# MPU6000.net
KiCad netlist of a schematic drawn in EAGLE
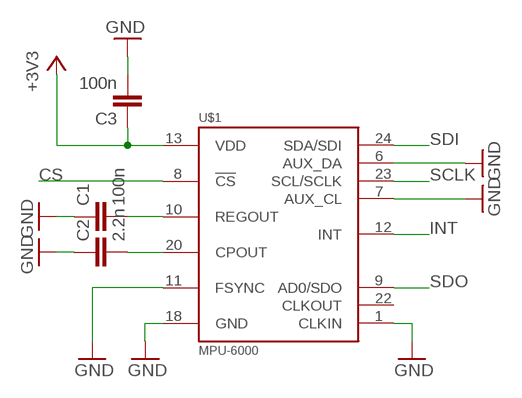
[diagram p0: schematic, sheet 1]

(export (version "E")
  (design (tool "Eeschema 10.0.6"))
  (components
    (comp (ref "C1")
      (value "100n")
      (footprint "eagle-import:C0805")
      (libsource (lib "eagle-import") (part "C-EUC0805"))
    )
    (comp (ref "C2")
      (value "2.2n")
      (footprint "eagle-import:C0805")
      (libsource (lib "eagle-import") (part "C-EUC0805"))
    )
    (comp (ref "C3")
      (value "100n")
      (footprint "eagle-import:C0805")
      (libsource (lib "eagle-import") (part "C-EUC0805"))
    )
    (comp (ref "U$1")
      (value "MPU-6000")
      (footprint "eagle-import:QFN-24")
      (fields (field (name "MF") "InvenSense"))
      (libsource (lib "eagle-import") (part "MPU-6000"))
    )
  )
  (nets
    (net (code "1") (name "+3V3") (class "Default")
      (node (ref "C3") (pin "1") (pinfunction "1_1") (pintype "passive"))
      (node (ref "U$1") (pin "13") (pinfunction "VDD_13") (pintype "bidirectional"))
    )
    (net (code "2") (name "/CS") (class "Default")
      (node (ref "U$1") (pin "8") (pinfunction "~{CS}_8") (pintype "bidirectional"))
    )
    (net (code "3") (name "/INT") (class "Default")
      (node (ref "U$1") (pin "12") (pinfunction "INT_12") (pintype "bidirectional"))
    )
    (net (code "4") (name "/SCLK") (class "Default")
      (node (ref "U$1") (pin "23") (pinfunction "SCL/SCLK_23") (pintype "bidirectional"))
    )
    (net (code "5") (name "/SDI") (class "Default")
      (node (ref "U$1") (pin "24") (pinfunction "SDA/SDI_24") (pintype "bidirectional"))
    )
    (net (code "6") (name "/SDO") (class "Default")
      (node (ref "U$1") (pin "9") (pinfunction "AD0/SDO_9") (pintype "bidirectional"))
    )
    (net (code "7") (name "GND") (class "Default")
      (node (ref "C1") (pin "1") (pinfunction "1_1") (pintype "passive"))
      (node (ref "C2") (pin "1") (pinfunction "1_1") (pintype "passive"))
      (node (ref "C3") (pin "2") (pinfunction "2_2") (pintype "passive"))
      (node (ref "U$1") (pin "1") (pinfunction "CLKIN_1") (pintype "bidirectional"))
      (node (ref "U$1") (pin "11") (pinfunction "FSYNC_11") (pintype "bidirectional"))
      (node (ref "U$1") (pin "18") (pinfunction "GND_18") (pintype "bidirectional"))
      (node (ref "U$1") (pin "6") (pinfunction "AUX_DA_6") (pintype "bidirectional"))
      (node (ref "U$1") (pin "7") (pinfunction "AUX_CL_7") (pintype "bidirectional"))
    )
    (net (code "8") (name "Net-(U$1-CPOUT)") (class "Default")
      (node (ref "C2") (pin "2") (pinfunction "2_2") (pintype "passive"))
      (node (ref "U$1") (pin "20") (pinfunction "CPOUT_20") (pintype "bidirectional"))
    )
    (net (code "9") (name "Net-(U$1-REGOUT)") (class "Default")
      (node (ref "C1") (pin "2") (pinfunction "2_2") (pintype "passive"))
      (node (ref "U$1") (pin "10") (pinfunction "REGOUT_10") (pintype "bidirectional"))
    )
    (net (code "10") (name "unconnected-(U$1-CLKOUT-Pad22)") (class "Default")
      (node (ref "U$1") (pin "22") (pinfunction "CLKOUT_22") (pintype "bidirectional"))
    )
  )
)
